# trippling.net
KiCad netlist of a schematic drawn in EAGLE
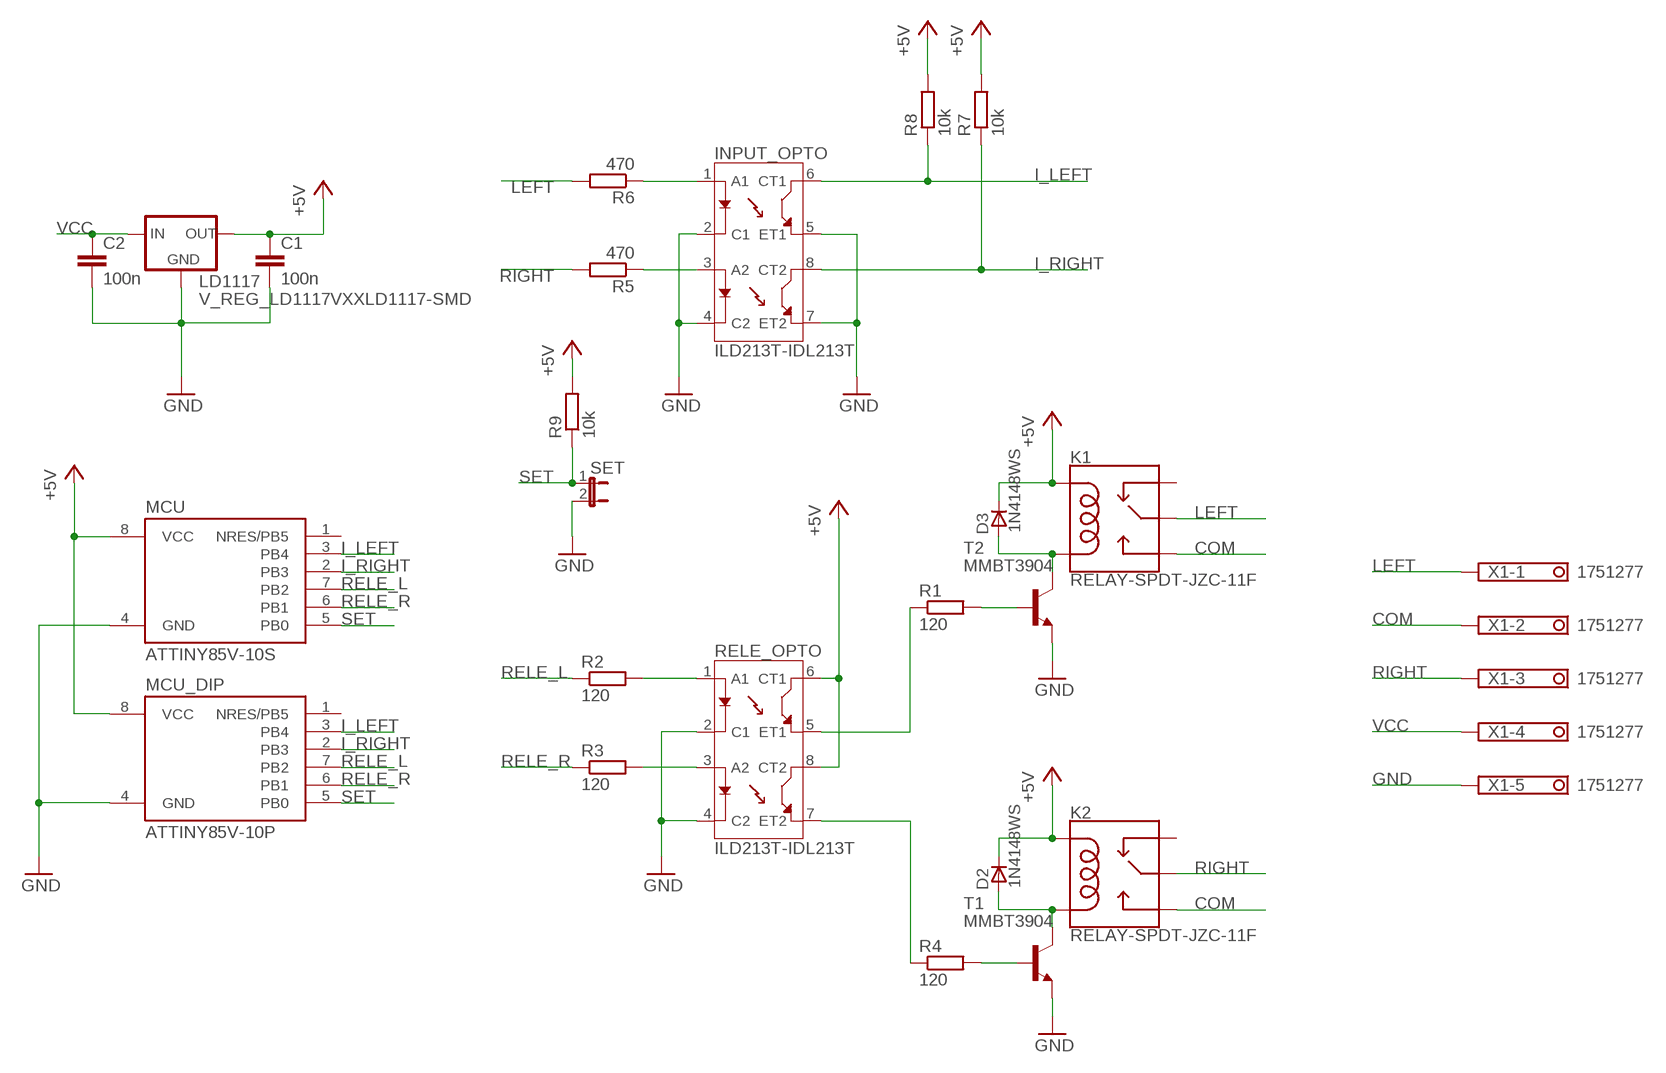
[diagram p0: schematic, sheet 1]

(export (version "E")
  (design (tool "Eeschema 10.0.6"))
  (components
    (comp (ref "C1")
      (value "100n")
      (footprint "eagle-import:C0805")
      (libsource (lib "eagle-import") (part "C-EUC0805"))
    )
    (comp (ref "C2")
      (value "100n")
      (footprint "eagle-import:C0805")
      (libsource (lib "eagle-import") (part "C-EUC0805"))
    )
    (comp (ref "D2")
      (value "1N4148WS")
      (footprint "eagle-import:SOD323F")
      (libsource (lib "eagle-import") (part "1N4148WS"))
    )
    (comp (ref "D3")
      (value "1N4148WS")
      (footprint "eagle-import:SOD323F")
      (libsource (lib "eagle-import") (part "1N4148WS"))
    )
    (comp (ref "INPUT_OPTO")
      (value "ILD213T-IDL213T")
      (footprint "eagle-import:SO08")
      (libsource (lib "eagle-import") (part "ILD213T-IDL213T"))
    )
    (comp (ref "K1")
      (value "RELAY-SPDT-JZC-11F")
      (footprint "eagle-import:RELAY-JZC")
      (libsource (lib "eagle-import") (part "RELAY-SPDT-JZC-11F"))
    )
    (comp (ref "K2")
      (value "RELAY-SPDT-JZC-11F")
      (footprint "eagle-import:RELAY-JZC")
      (libsource (lib "eagle-import") (part "RELAY-SPDT-JZC-11F"))
    )
    (comp (ref "LD1117")
      (value "V_REG_LD1117VXXLD1117-SMD")
      (footprint "eagle-import:SOT223")
      (libsource (lib "eagle-import") (part "V_REG_LD1117VXXLD1117-SMD"))
    )
    (comp (ref "MCU")
      (value "ATTINY85V-10S")
      (footprint "eagle-import:SOIC8_EIAJ_208MIL")
      (libsource (lib "eagle-import") (part "ATTINY85SV-10"))
    )
    (comp (ref "MCU_DIP")
      (value "ATTINY85V-10P")
      (footprint "eagle-import:PDIP08_300MIL")
      (libsource (lib "eagle-import") (part "ATTINY85PV-10"))
    )
    (comp (ref "R1")
      (value "120")
      (footprint "eagle-import:R0805")
      (libsource (lib "eagle-import") (part "R-EU_R0805"))
    )
    (comp (ref "R2")
      (value "120")
      (footprint "eagle-import:R0805")
      (libsource (lib "eagle-import") (part "R-EU_R0805"))
    )
    (comp (ref "R3")
      (value "120")
      (footprint "eagle-import:R0805")
      (libsource (lib "eagle-import") (part "R-EU_R0805"))
    )
    (comp (ref "R4")
      (value "120")
      (footprint "eagle-import:R0805")
      (libsource (lib "eagle-import") (part "R-EU_R0805"))
    )
    (comp (ref "R5")
      (value "470")
      (footprint "eagle-import:R0805")
      (libsource (lib "eagle-import") (part "R-EU_R0805"))
    )
    (comp (ref "R6")
      (value "470")
      (footprint "eagle-import:R0805")
      (libsource (lib "eagle-import") (part "R-EU_R0805"))
    )
    (comp (ref "R7")
      (value "10k")
      (footprint "eagle-import:R0805")
      (libsource (lib "eagle-import") (part "R-EU_R0805"))
    )
    (comp (ref "R8")
      (value "10k")
      (footprint "eagle-import:R0805")
      (libsource (lib "eagle-import") (part "R-EU_R0805"))
    )
    (comp (ref "R9")
      (value "10k")
      (footprint "eagle-import:R0805")
      (libsource (lib "eagle-import") (part "R-EU_R0805"))
    )
    (comp (ref "RELE_OPTO")
      (value "ILD213T-IDL213T")
      (footprint "eagle-import:SO08")
      (libsource (lib "eagle-import") (part "ILD213T-IDL213T"))
    )
    (comp (ref "SET")
      (value "JP1E")
      (footprint "eagle-import:JP1")
      (libsource (lib "eagle-import") (part "JP1E"))
    )
    (comp (ref "T1")
      (value "MMBT3904")
      (footprint "eagle-import:SOT23-BEC")
      (libsource (lib "eagle-import") (part "-NPN-SOT23-BECMMBT3904LT1"))
    )
    (comp (ref "T2")
      (value "MMBT3904")
      (footprint "eagle-import:SOT23-BEC")
      (libsource (lib "eagle-import") (part "-NPN-SOT23-BECMMBT3904LT1"))
    )
    (comp (ref "X1")
      (value "1751277")
      (footprint "eagle-import:1751277")
      (libsource (lib "eagle-import") (part "1751277"))
    )
  )
  (nets
    (net (code "1") (name "+5V") (class "Default")
      (node (ref "C1") (pin "1") (pinfunction "1_1") (pintype "passive"))
      (node (ref "D2") (pin "C") (pinfunction "C_C") (pintype "passive"))
      (node (ref "D3") (pin "C") (pinfunction "C_C") (pintype "passive"))
      (node (ref "K1") (pin "5") (pinfunction "COIL1_5") (pintype "bidirectional"))
      (node (ref "K2") (pin "5") (pinfunction "COIL1_5") (pintype "bidirectional"))
      (node (ref "LD1117") (pin "2") (pinfunction "OUT_2") (pintype "passive"))
      (node (ref "MCU") (pin "8") (pinfunction "VCC_8") (pintype "power_in"))
      (node (ref "MCU_DIP") (pin "8") (pinfunction "VCC_8") (pintype "power_in"))
      (node (ref "R7") (pin "2") (pinfunction "2_2") (pintype "passive"))
      (node (ref "R8") (pin "2") (pinfunction "2_2") (pintype "passive"))
      (node (ref "R9") (pin "2") (pinfunction "2_2") (pintype "passive"))
      (node (ref "RELE_OPTO") (pin "6") (pinfunction "CT1_6") (pintype "bidirectional"))
      (node (ref "RELE_OPTO") (pin "8") (pinfunction "CT2_8") (pintype "bidirectional"))
    )
    (net (code "2") (name "/COM") (class "Default")
      (node (ref "K1") (pin "3") (pinfunction "NO_3") (pintype "bidirectional"))
      (node (ref "K2") (pin "3") (pinfunction "NO_3") (pintype "bidirectional"))
      (node (ref "X1") (pin "2") (pinfunction "K_2") (pintype "passive"))
    )
    (net (code "3") (name "/I_LEFT") (class "Default")
      (node (ref "INPUT_OPTO") (pin "6") (pinfunction "CT1_6") (pintype "bidirectional"))
      (node (ref "MCU") (pin "3") (pinfunction "PB4_3") (pintype "bidirectional"))
      (node (ref "MCU_DIP") (pin "3") (pinfunction "PB4_3") (pintype "bidirectional"))
      (node (ref "R8") (pin "1") (pinfunction "1_1") (pintype "passive"))
    )
    (net (code "4") (name "/I_RIGHT") (class "Default")
      (node (ref "INPUT_OPTO") (pin "8") (pinfunction "CT2_8") (pintype "bidirectional"))
      (node (ref "MCU") (pin "2") (pinfunction "PB3_2") (pintype "bidirectional"))
      (node (ref "MCU_DIP") (pin "2") (pinfunction "PB3_2") (pintype "bidirectional"))
      (node (ref "R7") (pin "1") (pinfunction "1_1") (pintype "passive"))
    )
    (net (code "5") (name "/LEFT") (class "Default")
      (node (ref "K1") (pin "4") (pinfunction "MAIN_4") (pintype "bidirectional"))
      (node (ref "R6") (pin "2") (pinfunction "2_2") (pintype "passive"))
      (node (ref "X1") (pin "1") (pinfunction "K_1") (pintype "passive"))
    )
    (net (code "6") (name "/RELE_L") (class "Default")
      (node (ref "MCU") (pin "7") (pinfunction "PB2_7") (pintype "bidirectional"))
      (node (ref "MCU_DIP") (pin "7") (pinfunction "PB2_7") (pintype "bidirectional"))
      (node (ref "R2") (pin "1") (pinfunction "1_1") (pintype "passive"))
    )
    (net (code "7") (name "/RELE_R") (class "Default")
      (node (ref "MCU") (pin "6") (pinfunction "PB1_6") (pintype "bidirectional"))
      (node (ref "MCU_DIP") (pin "6") (pinfunction "PB1_6") (pintype "bidirectional"))
      (node (ref "R3") (pin "1") (pinfunction "1_1") (pintype "passive"))
    )
    (net (code "8") (name "/RIGHT") (class "Default")
      (node (ref "K2") (pin "4") (pinfunction "MAIN_4") (pintype "bidirectional"))
      (node (ref "R5") (pin "2") (pinfunction "2_2") (pintype "passive"))
      (node (ref "X1") (pin "3") (pinfunction "K_3") (pintype "passive"))
    )
    (net (code "9") (name "/SET") (class "Default")
      (node (ref "MCU") (pin "5") (pinfunction "PB0_5") (pintype "bidirectional"))
      (node (ref "MCU_DIP") (pin "5") (pinfunction "PB0_5") (pintype "bidirectional"))
      (node (ref "R9") (pin "1") (pinfunction "1_1") (pintype "passive"))
      (node (ref "SET") (pin "1") (pinfunction "1_1") (pintype "passive"))
    )
    (net (code "10") (name "/VCC") (class "Default")
      (node (ref "C2") (pin "1") (pinfunction "1_1") (pintype "passive"))
      (node (ref "LD1117") (pin "3") (pinfunction "IN_3") (pintype "input"))
      (node (ref "X1") (pin "4") (pinfunction "K_4") (pintype "passive"))
    )
    (net (code "11") (name "GND") (class "Default")
      (node (ref "C1") (pin "2") (pinfunction "2_2") (pintype "passive"))
      (node (ref "C2") (pin "2") (pinfunction "2_2") (pintype "passive"))
      (node (ref "INPUT_OPTO") (pin "2") (pinfunction "C1_2") (pintype "bidirectional"))
      (node (ref "INPUT_OPTO") (pin "4") (pinfunction "C2_4") (pintype "bidirectional"))
      (node (ref "INPUT_OPTO") (pin "5") (pinfunction "ET1_5") (pintype "bidirectional"))
      (node (ref "INPUT_OPTO") (pin "7") (pinfunction "ET2_7") (pintype "bidirectional"))
      (node (ref "LD1117") (pin "1") (pinfunction "GND_1") (pintype "input"))
      (node (ref "MCU") (pin "4") (pinfunction "GND_4") (pintype "power_in"))
      (node (ref "MCU_DIP") (pin "4") (pinfunction "GND_4") (pintype "power_in"))
      (node (ref "RELE_OPTO") (pin "2") (pinfunction "C1_2") (pintype "bidirectional"))
      (node (ref "RELE_OPTO") (pin "4") (pinfunction "C2_4") (pintype "bidirectional"))
      (node (ref "SET") (pin "2") (pinfunction "2_2") (pintype "passive"))
      (node (ref "T1") (pin "E") (pinfunction "E_E") (pintype "passive"))
      (node (ref "T2") (pin "E") (pinfunction "E_E") (pintype "passive"))
      (node (ref "X1") (pin "5") (pinfunction "K_5") (pintype "passive"))
    )
    (net (code "12") (name "Net-(INPUT_OPTO-A1)") (class "Default")
      (node (ref "INPUT_OPTO") (pin "1") (pinfunction "A1_1") (pintype "bidirectional"))
      (node (ref "R6") (pin "1") (pinfunction "1_1") (pintype "passive"))
    )
    (net (code "13") (name "Net-(INPUT_OPTO-A2)") (class "Default")
      (node (ref "INPUT_OPTO") (pin "3") (pinfunction "A2_3") (pintype "bidirectional"))
      (node (ref "R5") (pin "1") (pinfunction "1_1") (pintype "passive"))
    )
    (net (code "14") (name "Net-(K1-COIL2)") (class "Default")
      (node (ref "D3") (pin "A") (pinfunction "A_A") (pintype "passive"))
      (node (ref "K1") (pin "1") (pinfunction "COIL2_1") (pintype "bidirectional"))
      (node (ref "T2") (pin "C") (pinfunction "C_C") (pintype "passive"))
    )
    (net (code "15") (name "Net-(K2-COIL2)") (class "Default")
      (node (ref "D2") (pin "A") (pinfunction "A_A") (pintype "passive"))
      (node (ref "K2") (pin "1") (pinfunction "COIL2_1") (pintype "bidirectional"))
      (node (ref "T1") (pin "C") (pinfunction "C_C") (pintype "passive"))
    )
    (net (code "16") (name "Net-(R1-Pad2)") (class "Default")
      (node (ref "R1") (pin "2") (pinfunction "2_2") (pintype "passive"))
      (node (ref "T2") (pin "B") (pinfunction "B_B") (pintype "passive"))
    )
    (net (code "17") (name "Net-(R4-Pad2)") (class "Default")
      (node (ref "R4") (pin "2") (pinfunction "2_2") (pintype "passive"))
      (node (ref "T1") (pin "B") (pinfunction "B_B") (pintype "passive"))
    )
    (net (code "18") (name "Net-(RELE_OPTO-A1)") (class "Default")
      (node (ref "R2") (pin "2") (pinfunction "2_2") (pintype "passive"))
      (node (ref "RELE_OPTO") (pin "1") (pinfunction "A1_1") (pintype "bidirectional"))
    )
    (net (code "19") (name "Net-(RELE_OPTO-A2)") (class "Default")
      (node (ref "R3") (pin "2") (pinfunction "2_2") (pintype "passive"))
      (node (ref "RELE_OPTO") (pin "3") (pinfunction "A2_3") (pintype "bidirectional"))
    )
    (net (code "20") (name "Net-(RELE_OPTO-ET1)") (class "Default")
      (node (ref "R1") (pin "1") (pinfunction "1_1") (pintype "passive"))
      (node (ref "RELE_OPTO") (pin "5") (pinfunction "ET1_5") (pintype "bidirectional"))
    )
    (net (code "21") (name "Net-(RELE_OPTO-ET2)") (class "Default")
      (node (ref "R4") (pin "1") (pinfunction "1_1") (pintype "passive"))
      (node (ref "RELE_OPTO") (pin "7") (pinfunction "ET2_7") (pintype "bidirectional"))
    )
    (net (code "22") (name "unconnected-(K1-NC-Pad2)") (class "Default")
      (node (ref "K1") (pin "2") (pinfunction "NC_2") (pintype "bidirectional"))
    )
    (net (code "23") (name "unconnected-(K2-NC-Pad2)") (class "Default")
      (node (ref "K2") (pin "2") (pinfunction "NC_2") (pintype "bidirectional"))
    )
    (net (code "24") (name "unconnected-(MCU-NRES{slash}PB5-Pad1)") (class "Default")
      (node (ref "MCU") (pin "1") (pinfunction "NRES/PB5_1") (pintype "bidirectional"))
    )
    (net (code "25") (name "unconnected-(MCU_DIP-NRES{slash}PB5-Pad1)") (class "Default")
      (node (ref "MCU_DIP") (pin "1") (pinfunction "NRES/PB5_1") (pintype "bidirectional"))
    )
  )
)
